# MosfetV5.net
KiCad netlist of a schematic drawn in EAGLE
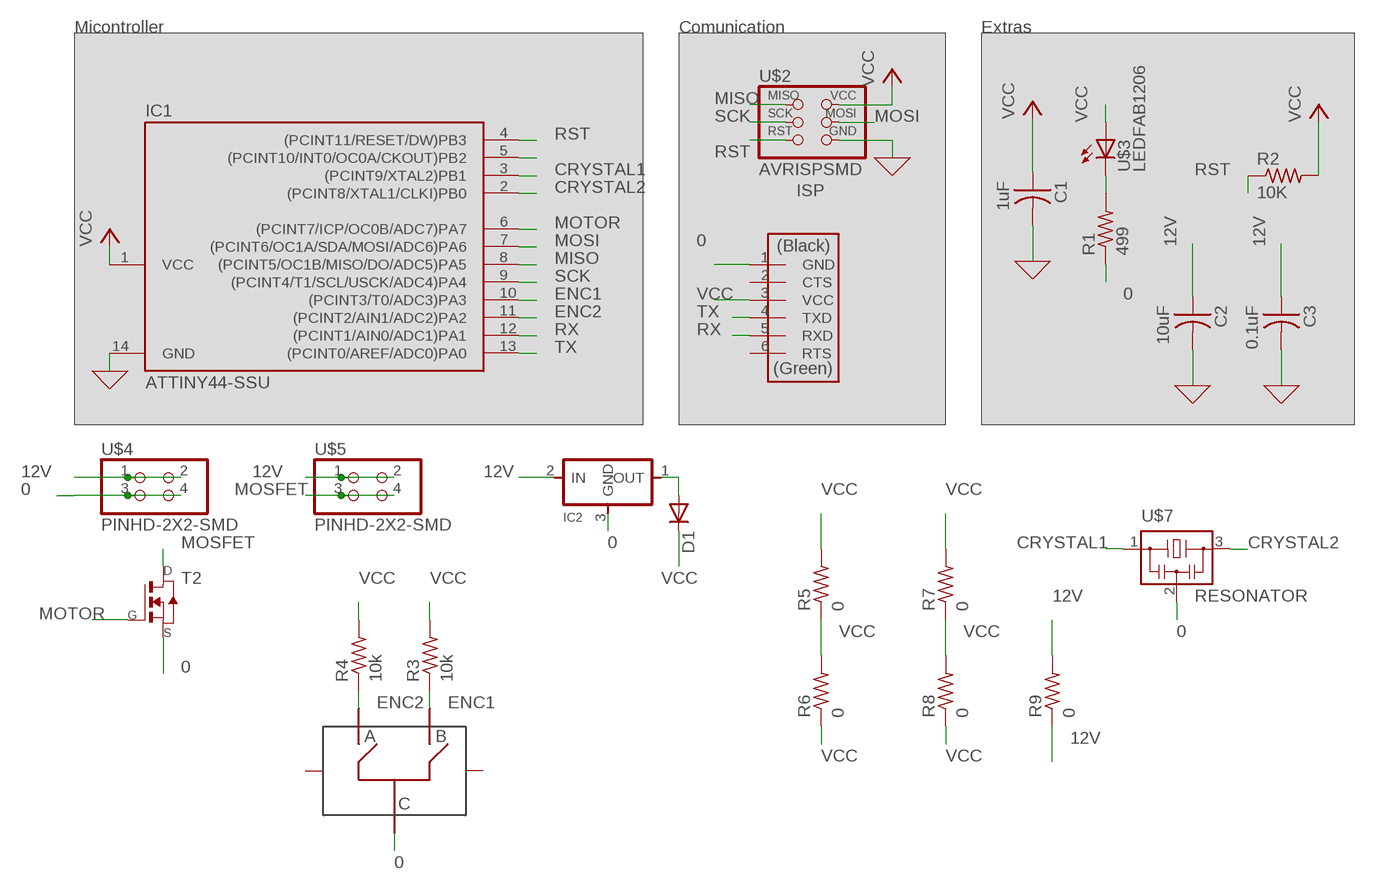
[diagram p0: schematic, sheet 1]

(export (version "E")
  (design (tool "Eeschema 10.0.6"))
  (components
    (comp (ref "C1")
      (value "1uF")
      (footprint "eagle-import:C1206FAB")
      (libsource (lib "eagle-import") (part "CAP-US1206FAB"))
    )
    (comp (ref "C2")
      (value "10uF")
      (footprint "eagle-import:C1206FAB")
      (libsource (lib "eagle-import") (part "CAP-US1206FAB"))
    )
    (comp (ref "C3")
      (value "0.1uF")
      (footprint "eagle-import:C1206FAB")
      (libsource (lib "eagle-import") (part "CAP-US1206FAB"))
    )
    (comp (ref "D1")
      (value "DIODESOD123")
      (footprint "eagle-import:SOD123")
      (libsource (lib "eagle-import") (part "DIODESOD123"))
    )
    (comp (ref "IC1")
      (value "ATTINY44-SSU")
      (footprint "eagle-import:SOIC14")
      (libsource (lib "eagle-import") (part "ATTINY44-SSU"))
    )
    (comp (ref "IC2")
      (value "REGULATORSOT23")
      (footprint "eagle-import:SOT23")
      (libsource (lib "eagle-import") (part "REGULATORSOT23"))
    )
    (comp (ref "R1")
      (value "499")
      (footprint "eagle-import:R1206FAB")
      (libsource (lib "eagle-import") (part "RES-US1206FAB"))
    )
    (comp (ref "R2")
      (value "10K")
      (footprint "eagle-import:R1206FAB")
      (libsource (lib "eagle-import") (part "RES-US1206FAB"))
    )
    (comp (ref "R3")
      (value "10k")
      (footprint "eagle-import:R1206FAB")
      (libsource (lib "eagle-import") (part "RES-US1206FAB"))
    )
    (comp (ref "R4")
      (value "10k")
      (footprint "eagle-import:R1206FAB")
      (libsource (lib "eagle-import") (part "RES-US1206FAB"))
    )
    (comp (ref "R5")
      (value "0")
      (footprint "eagle-import:R1206FAB")
      (libsource (lib "eagle-import") (part "RES-US1206FAB"))
    )
    (comp (ref "R6")
      (value "0")
      (footprint "eagle-import:R1206FAB")
      (libsource (lib "eagle-import") (part "RES-US1206FAB"))
    )
    (comp (ref "R7")
      (value "0")
      (footprint "eagle-import:R1206FAB")
      (libsource (lib "eagle-import") (part "RES-US1206FAB"))
    )
    (comp (ref "R8")
      (value "0")
      (footprint "eagle-import:R1206FAB")
      (libsource (lib "eagle-import") (part "RES-US1206FAB"))
    )
    (comp (ref "R9")
      (value "0")
      (footprint "eagle-import:R1206FAB")
      (libsource (lib "eagle-import") (part "RES-US1206FAB"))
    )
    (comp (ref "T2")
      (value "NMOSFETTO252")
      (footprint "eagle-import:TO252")
      (libsource (lib "eagle-import") (part "NMOSFETTO252"))
    )
    (comp (ref "U$1")
      (value "FTDI-SMD-HEADER")
      (footprint "eagle-import:1X06SMD")
      (libsource (lib "eagle-import") (part "FTDI-SMD-HEADER"))
    )
    (comp (ref "U$2")
      (value "AVRISPSMD")
      (footprint "eagle-import:2X03SMD")
      (libsource (lib "eagle-import") (part "AVRISPSMD"))
    )
    (comp (ref "U$3")
      (value "LEDFAB1206")
      (footprint "eagle-import:LED1206FAB")
      (libsource (lib "eagle-import") (part "LEDFAB1206"))
    )
    (comp (ref "U$4")
      (value "PINHD-2X2-SMD")
      (footprint "eagle-import:2X02SMD")
      (libsource (lib "eagle-import") (part "PINHD-2X2-SMD"))
    )
    (comp (ref "U$5")
      (value "PINHD-2X2-SMD")
      (footprint "eagle-import:2X02SMD")
      (libsource (lib "eagle-import") (part "PINHD-2X2-SMD"))
    )
    (comp (ref "U$6")
      (value "ALBS_ENCODER_STEC12E08")
      (footprint "eagle-import:STEC12E08")
      (libsource (lib "eagle-import") (part "ALBS_ENCODER_STEC12E08"))
    )
    (comp (ref "U$7")
      (value "RESONATOR")
      (footprint "eagle-import:EFOBM")
      (libsource (lib "eagle-import") (part "RESONATOR"))
    )
  )
  (nets
    (net (code "1") (name "/12V") (class "Default")
      (node (ref "C2") (pin "1") (pinfunction "1_1") (pintype "passive"))
      (node (ref "C3") (pin "1") (pinfunction "1_1") (pintype "passive"))
      (node (ref "IC2") (pin "2") (pinfunction "IN_2") (pintype "bidirectional"))
      (node (ref "R9") (pin "1") (pinfunction "1_1") (pintype "passive"))
      (node (ref "R9") (pin "2") (pinfunction "2_2") (pintype "passive"))
      (node (ref "U$4") (pin "1") (pinfunction "1_1") (pintype "passive"))
      (node (ref "U$4") (pin "2") (pinfunction "2_2") (pintype "passive"))
      (node (ref "U$5") (pin "1") (pinfunction "1_1") (pintype "passive"))
      (node (ref "U$5") (pin "2") (pinfunction "2_2") (pintype "passive"))
    )
    (net (code "2") (name "/CRYSTAL1") (class "Default")
      (node (ref "IC1") (pin "3") (pinfunction "(PCINT9/XTAL2)PB1_3") (pintype "bidirectional"))
      (node (ref "U$7") (pin "1") (pinfunction "1_1") (pintype "passive"))
    )
    (net (code "3") (name "/CRYSTAL2") (class "Default")
      (node (ref "IC1") (pin "2") (pinfunction "(PCINT8/XTAL1/CLKI)PB0_2") (pintype "bidirectional"))
      (node (ref "U$7") (pin "3") (pinfunction "3_3") (pintype "passive"))
    )
    (net (code "4") (name "/ENC1") (class "Default")
      (node (ref "IC1") (pin "10") (pinfunction "(PCINT3/T0/ADC3)PA3_10") (pintype "bidirectional"))
      (node (ref "R3") (pin "1") (pinfunction "1_1") (pintype "passive"))
      (node (ref "U$6") (pin "P$B") (pinfunction "TERMINAL_B_P$B") (pintype "bidirectional"))
    )
    (net (code "5") (name "/ENC2") (class "Default")
      (node (ref "IC1") (pin "11") (pinfunction "(PCINT2/AIN1/ADC2)PA2_11") (pintype "bidirectional"))
      (node (ref "R4") (pin "1") (pinfunction "1_1") (pintype "passive"))
      (node (ref "U$6") (pin "P$A") (pinfunction "TERMINAL_A_P$A") (pintype "bidirectional"))
    )
    (net (code "6") (name "/MISO") (class "Default")
      (node (ref "IC1") (pin "8") (pinfunction "(PCINT5/OC1B/MISO/DO/ADC5)PA5_8") (pintype "bidirectional"))
      (node (ref "U$2") (pin "1") (pinfunction "MISO_1") (pintype "passive"))
    )
    (net (code "7") (name "/MOSFET") (class "Default")
      (node (ref "T2") (pin "3") (pinfunction "D_3") (pintype "passive"))
      (node (ref "U$5") (pin "3") (pinfunction "3_3") (pintype "passive"))
      (node (ref "U$5") (pin "4") (pinfunction "4_4") (pintype "passive"))
    )
    (net (code "8") (name "/MOSI") (class "Default")
      (node (ref "IC1") (pin "7") (pinfunction "(PCINT6/OC1A/SDA/MOSI/ADC6)PA6_7") (pintype "bidirectional"))
      (node (ref "U$2") (pin "4") (pinfunction "MOSI_4") (pintype "passive"))
    )
    (net (code "9") (name "/MOTOR") (class "Default")
      (node (ref "IC1") (pin "6") (pinfunction "(PCINT7/ICP/OC0B/ADC7)PA7_6") (pintype "bidirectional"))
      (node (ref "T2") (pin "1") (pinfunction "G_1") (pintype "passive"))
    )
    (net (code "10") (name "/RST") (class "Default")
      (node (ref "IC1") (pin "4") (pinfunction "(PCINT11/RESET/DW)PB3_4") (pintype "bidirectional"))
      (node (ref "R2") (pin "1") (pinfunction "1_1") (pintype "passive"))
      (node (ref "U$2") (pin "5") (pinfunction "RST_5") (pintype "passive"))
    )
    (net (code "11") (name "/RX") (class "Default")
      (node (ref "IC1") (pin "12") (pinfunction "(PCINT1/AIN0/ADC1)PA1_12") (pintype "bidirectional"))
      (node (ref "U$1") (pin "5") (pinfunction "RXD_5") (pintype "bidirectional"))
    )
    (net (code "12") (name "/SCK") (class "Default")
      (node (ref "IC1") (pin "9") (pinfunction "(PCINT4/T1/SCL/USCK/ADC4)PA4_9") (pintype "bidirectional"))
      (node (ref "U$2") (pin "3") (pinfunction "SCK_3") (pintype "passive"))
    )
    (net (code "13") (name "/TX") (class "Default")
      (node (ref "IC1") (pin "13") (pinfunction "(PCINT0/AREF/ADC0)PA0_13") (pintype "bidirectional"))
      (node (ref "U$1") (pin "4") (pinfunction "TXD_4") (pintype "bidirectional"))
    )
    (net (code "14") (name "GND") (class "Default")
      (node (ref "C1") (pin "2") (pinfunction "2_2") (pintype "passive"))
      (node (ref "C2") (pin "2") (pinfunction "2_2") (pintype "passive"))
      (node (ref "C3") (pin "2") (pinfunction "2_2") (pintype "passive"))
      (node (ref "IC1") (pin "14") (pinfunction "GND_14") (pintype "power_in"))
      (node (ref "IC2") (pin "3") (pinfunction "GND_3") (pintype "bidirectional"))
      (node (ref "R1") (pin "1") (pinfunction "1_1") (pintype "passive"))
      (node (ref "T2") (pin "2") (pinfunction "S_2") (pintype "passive"))
      (node (ref "U$1") (pin "1") (pinfunction "GND_1") (pintype "bidirectional"))
      (node (ref "U$2") (pin "6") (pinfunction "GND_6") (pintype "passive"))
      (node (ref "U$4") (pin "3") (pinfunction "3_3") (pintype "passive"))
      (node (ref "U$4") (pin "4") (pinfunction "4_4") (pintype "passive"))
      (node (ref "U$6") (pin "P$C") (pinfunction "TERMINAL_C_P$C") (pintype "bidirectional"))
      (node (ref "U$7") (pin "2") (pinfunction "2_2") (pintype "passive"))
    )
    (net (code "15") (name "Net-(D1-A)") (class "Default")
      (node (ref "D1") (pin "ANODE") (pinfunction "A_ANODE") (pintype "passive"))
      (node (ref "IC2") (pin "1") (pinfunction "OUT_1") (pintype "bidirectional"))
    )
    (net (code "16") (name "Net-(U$3-C)") (class "Default")
      (node (ref "R1") (pin "2") (pinfunction "2_2") (pintype "passive"))
      (node (ref "U$3") (pin "2") (pinfunction "C_2") (pintype "passive"))
    )
    (net (code "17") (name "VCC") (class "Default")
      (node (ref "C1") (pin "1") (pinfunction "1_1") (pintype "passive"))
      (node (ref "D1") (pin "CATHODE") (pinfunction "C_CATHODE") (pintype "passive"))
      (node (ref "IC1") (pin "1") (pinfunction "VCC_1") (pintype "power_in"))
      (node (ref "R2") (pin "2") (pinfunction "2_2") (pintype "passive"))
      (node (ref "R3") (pin "2") (pinfunction "2_2") (pintype "passive"))
      (node (ref "R4") (pin "2") (pinfunction "2_2") (pintype "passive"))
      (node (ref "R5") (pin "1") (pinfunction "1_1") (pintype "passive"))
      (node (ref "R5") (pin "2") (pinfunction "2_2") (pintype "passive"))
      (node (ref "R6") (pin "1") (pinfunction "1_1") (pintype "passive"))
      (node (ref "R6") (pin "2") (pinfunction "2_2") (pintype "passive"))
      (node (ref "R7") (pin "1") (pinfunction "1_1") (pintype "passive"))
      (node (ref "R7") (pin "2") (pinfunction "2_2") (pintype "passive"))
      (node (ref "R8") (pin "1") (pinfunction "1_1") (pintype "passive"))
      (node (ref "R8") (pin "2") (pinfunction "2_2") (pintype "passive"))
      (node (ref "U$1") (pin "3") (pinfunction "VCC_3") (pintype "bidirectional"))
      (node (ref "U$2") (pin "2") (pinfunction "VCC_2") (pintype "passive"))
      (node (ref "U$3") (pin "1") (pinfunction "A_1") (pintype "passive"))
    )
    (net (code "18") (name "unconnected-(IC1-(PCINT10{slash}INT0{slash}OC0A{slash}CKOUT)PB2-Pad5)") (class "Default")
      (node (ref "IC1") (pin "5") (pinfunction "(PCINT10/INT0/OC0A/CKOUT)PB2_5") (pintype "bidirectional"))
    )
    (net (code "19") (name "unconnected-(U$1-CTS-Pad2)") (class "Default")
      (node (ref "U$1") (pin "2") (pinfunction "CTS_2") (pintype "bidirectional"))
    )
    (net (code "20") (name "unconnected-(U$1-RTS-Pad6)") (class "Default")
      (node (ref "U$1") (pin "6") (pinfunction "RTS_6") (pintype "bidirectional"))
    )
    (net (code "21") (name "unconnected-(U$6-PadP$CASE0)") (class "Default")
      (node (ref "U$6") (pin "P$CASE0") (pinfunction "P$CASE0_P$CASE0") (pintype "bidirectional"))
    )
    (net (code "22") (name "unconnected-(U$6-PadP$CASE1)") (class "Default")
      (node (ref "U$6") (pin "P$CASE1") (pinfunction "P$CASE1_P$CASE1") (pintype "bidirectional"))
    )
  )
)
